# IHM.net
KiCad netlist of a schematic drawn in Altium Designer
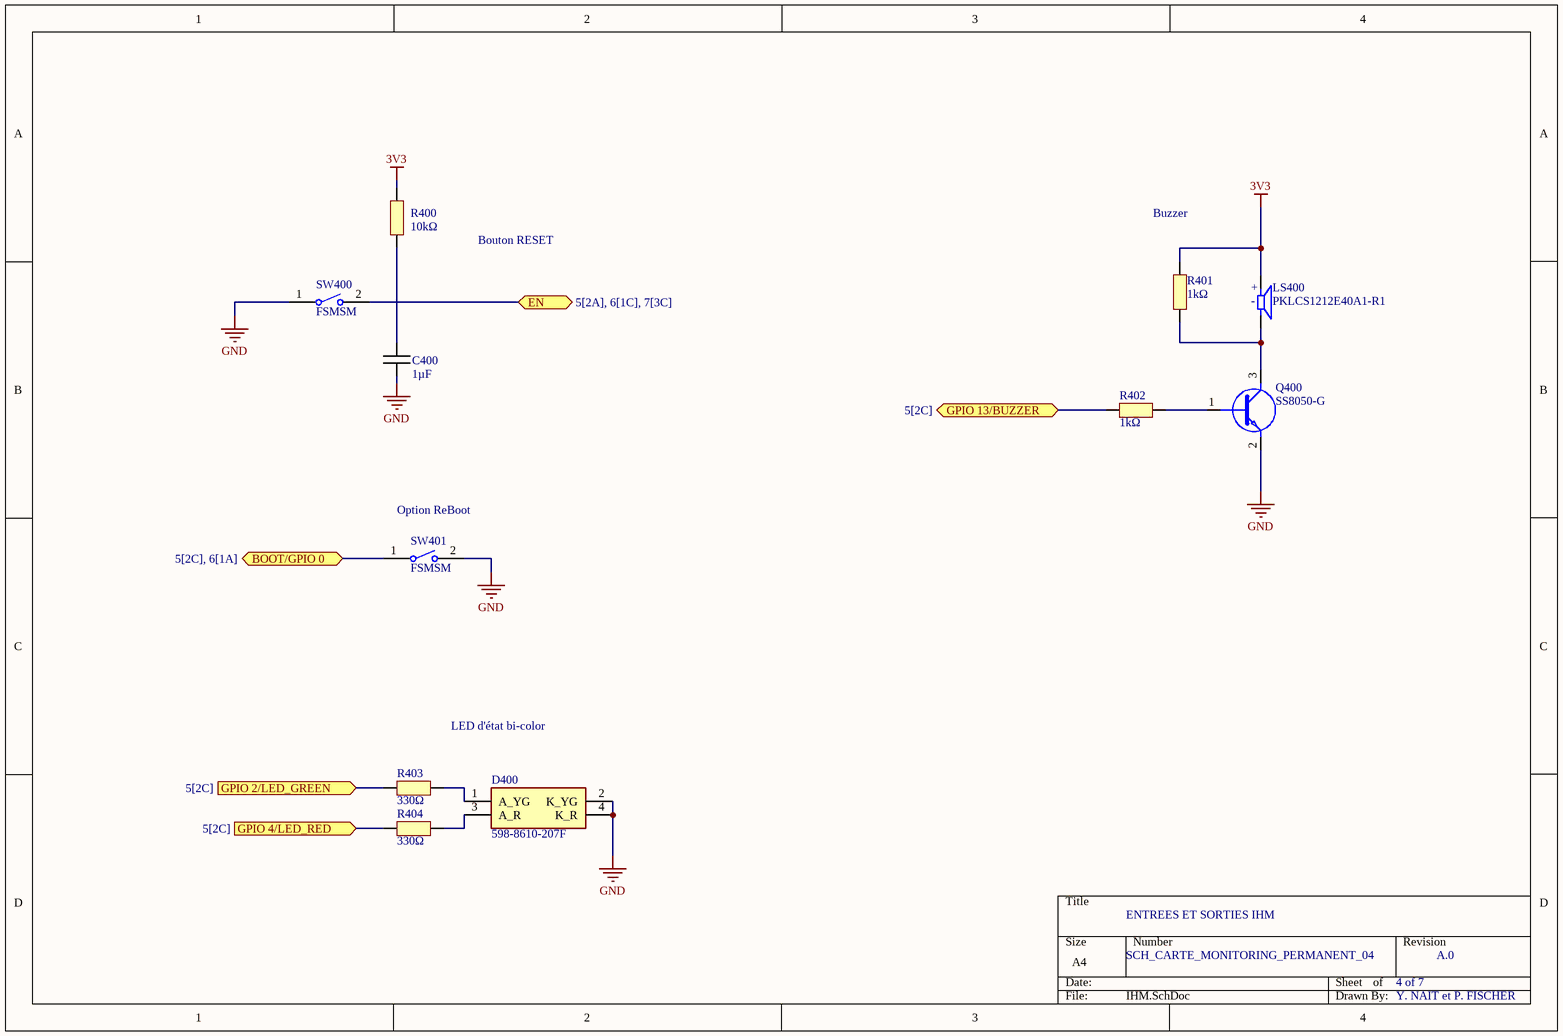
[diagram p0: IHM.SchDoc]

(export (version "E")
  (design (tool "Eeschema 10.0.6"))
  (components
    (comp (ref "C400")
      (value "1µF")
      (footprint "CAPC1005X06N")
      (libsource (lib "SCHLibrary") (part "Capacitor"))
    )
    (comp (ref "D400")
      (value "598-8610-207F")
      (footprint "5988610207F")
      (description "Standard LEDs - SMD Red/Green WC 80/50mcd 645/570nm")
      (fields (field (name "MOUSER PART NUMBER") "645-598-8610-207F"))
      (libsource (lib "SCHLibrary") (part "598-8610-207F"))
    )
    (comp (ref "LS400")
      (value "PKLCS1212E40A1-R1")
      (footprint "SPKR_PKLCS1212E40A1-R1")
      (description "Buzzers Transducer, Externally Driven Piezo 1.5V 2kHz 70dB @ 1.5V, 10cm Surface Mount Solder Pads")
      (fields (field (name "MF") "Murata Electronics"))
      (libsource (lib "SCHLibrary") (part "PKLCS1212E40A1-R1"))
    )
    (comp (ref "Q400")
      (value "SS8050-G")
      (footprint "SS8050-G")
      (description "Bipolar Transistors - BJT NPN TRANSISTOR 1.5A 40V")
      (libsource (lib "SCHLibrary") (part "SS8050-G"))
    )
    (comp (ref "R400")
      (value "10kΩ")
      (footprint "RESC1005X06N")
      (libsource (lib "SCHLibrary") (part "Resistor"))
    )
    (comp (ref "R401")
      (value "1kΩ")
      (footprint "RESC1005X06N")
      (libsource (lib "SCHLibrary") (part "Resistor"))
    )
    (comp (ref "R402") (value "1kΩ") (footprint "RESC1005X06N") (libsource (lib "") (part "Resistor_1")))
    (comp (ref "R403") (value "330Ω") (footprint "RESC1005X06N") (libsource (lib "") (part "Resistor_1")))
    (comp (ref "R404") (value "330Ω") (footprint "RESC1005X06N") (libsource (lib "") (part "Resistor_1")))
    (comp (ref "SW400")
      (value "FSMSM")
      (footprint "TECO-FSMSM-2_V")
      (description "FSMSM Push Button Switch, 50 mA, -35 to 85 degC, 2-Pin SMD, RoHS, Bulk")
      (fields (field (name "MANUFACTURER") "TE Connectivity"))
      (libsource (lib "SCHLibrary") (part "CMP-2000-07511-1"))
    )
    (comp (ref "SW401")
      (value "FSMSM")
      (footprint "TECO-FSMSM-2_V")
      (description "FSMSM Push Button Switch, 50 mA, -35 to 85 degC, 2-Pin SMD, RoHS, Bulk")
      (fields (field (name "MANUFACTURER") "TE Connectivity"))
      (libsource (lib "SCHLibrary") (part "CMP-2000-07511-1"))
    )
  )
  (nets
    (net (code "1") (name "/BOOT{slash}GPIO 0") (class "Default")
      (node (ref "SW401") (pin "1") (pinfunction "1_1") (pintype "passive"))
    )
    (net (code "2") (name "/EN") (class "Default")
      (node (ref "SW400") (pin "2") (pinfunction "2_2") (pintype "passive"))
    )
    (net (code "3") (name "/GPIO 2{slash}LED_GREEN") (class "Default")
      (node (ref "R403") (pin "1") (pinfunction "1_1") (pintype "passive"))
    )
    (net (code "4") (name "/GPIO 4{slash}LED_RED") (class "Default")
      (node (ref "R404") (pin "1") (pinfunction "1_1") (pintype "passive"))
    )
    (net (code "5") (name "/GPIO 13{slash}BUZZER") (class "Default")
      (node (ref "R402") (pin "1") (pinfunction "1_1") (pintype "passive"))
    )
    (net (code "6") (name "3V3") (class "Default")
      (node (ref "LS400") (pin "P") (pinfunction "P_P") (pintype "passive"))
      (node (ref "R400") (pin "2") (pinfunction "2_2") (pintype "passive"))
      (node (ref "R401") (pin "2") (pinfunction "2_2") (pintype "passive"))
    )
    (net (code "7") (name "GND") (class "Default")
      (node (ref "C400") (pin "2") (pinfunction "2_2") (pintype "passive"))
      (node (ref "D400") (pin "2") (pinfunction "K_YG_2") (pintype "passive"))
      (node (ref "D400") (pin "4") (pinfunction "K_R_4") (pintype "passive"))
      (node (ref "Q400") (pin "2") (pinfunction "E_2") (pintype "passive"))
      (node (ref "SW400") (pin "1") (pinfunction "1_1") (pintype "passive"))
      (node (ref "SW401") (pin "2") (pinfunction "2_2") (pintype "passive"))
    )
    (net (code "8") (name "Net-(C400-Pad1)") (class "Default")
      (node (ref "C400") (pin "1") (pinfunction "1_1") (pintype "passive"))
      (node (ref "R400") (pin "1") (pinfunction "1_1") (pintype "passive"))
    )
    (net (code "9") (name "Net-(D400-A_R)") (class "Default")
      (node (ref "D400") (pin "3") (pinfunction "A_R_3") (pintype "passive"))
      (node (ref "R404") (pin "2") (pinfunction "2_2") (pintype "passive"))
    )
    (net (code "10") (name "Net-(D400-A_YG)") (class "Default")
      (node (ref "D400") (pin "1") (pinfunction "A_YG_1") (pintype "passive"))
      (node (ref "R403") (pin "2") (pinfunction "2_2") (pintype "passive"))
    )
    (net (code "11") (name "Net-(Q400-B)") (class "Default")
      (node (ref "Q400") (pin "1") (pinfunction "B_1") (pintype "passive"))
      (node (ref "R402") (pin "2") (pinfunction "2_2") (pintype "passive"))
    )
    (net (code "12") (name "Net-(Q400-C)") (class "Default")
      (node (ref "LS400") (pin "N") (pinfunction "N_N") (pintype "passive"))
      (node (ref "Q400") (pin "3") (pinfunction "C_3") (pintype "passive"))
      (node (ref "R401") (pin "1") (pinfunction "1_1") (pintype "passive"))
    )
  )
)
